# TimerModule.net
KiCad netlist of a schematic drawn in EAGLE
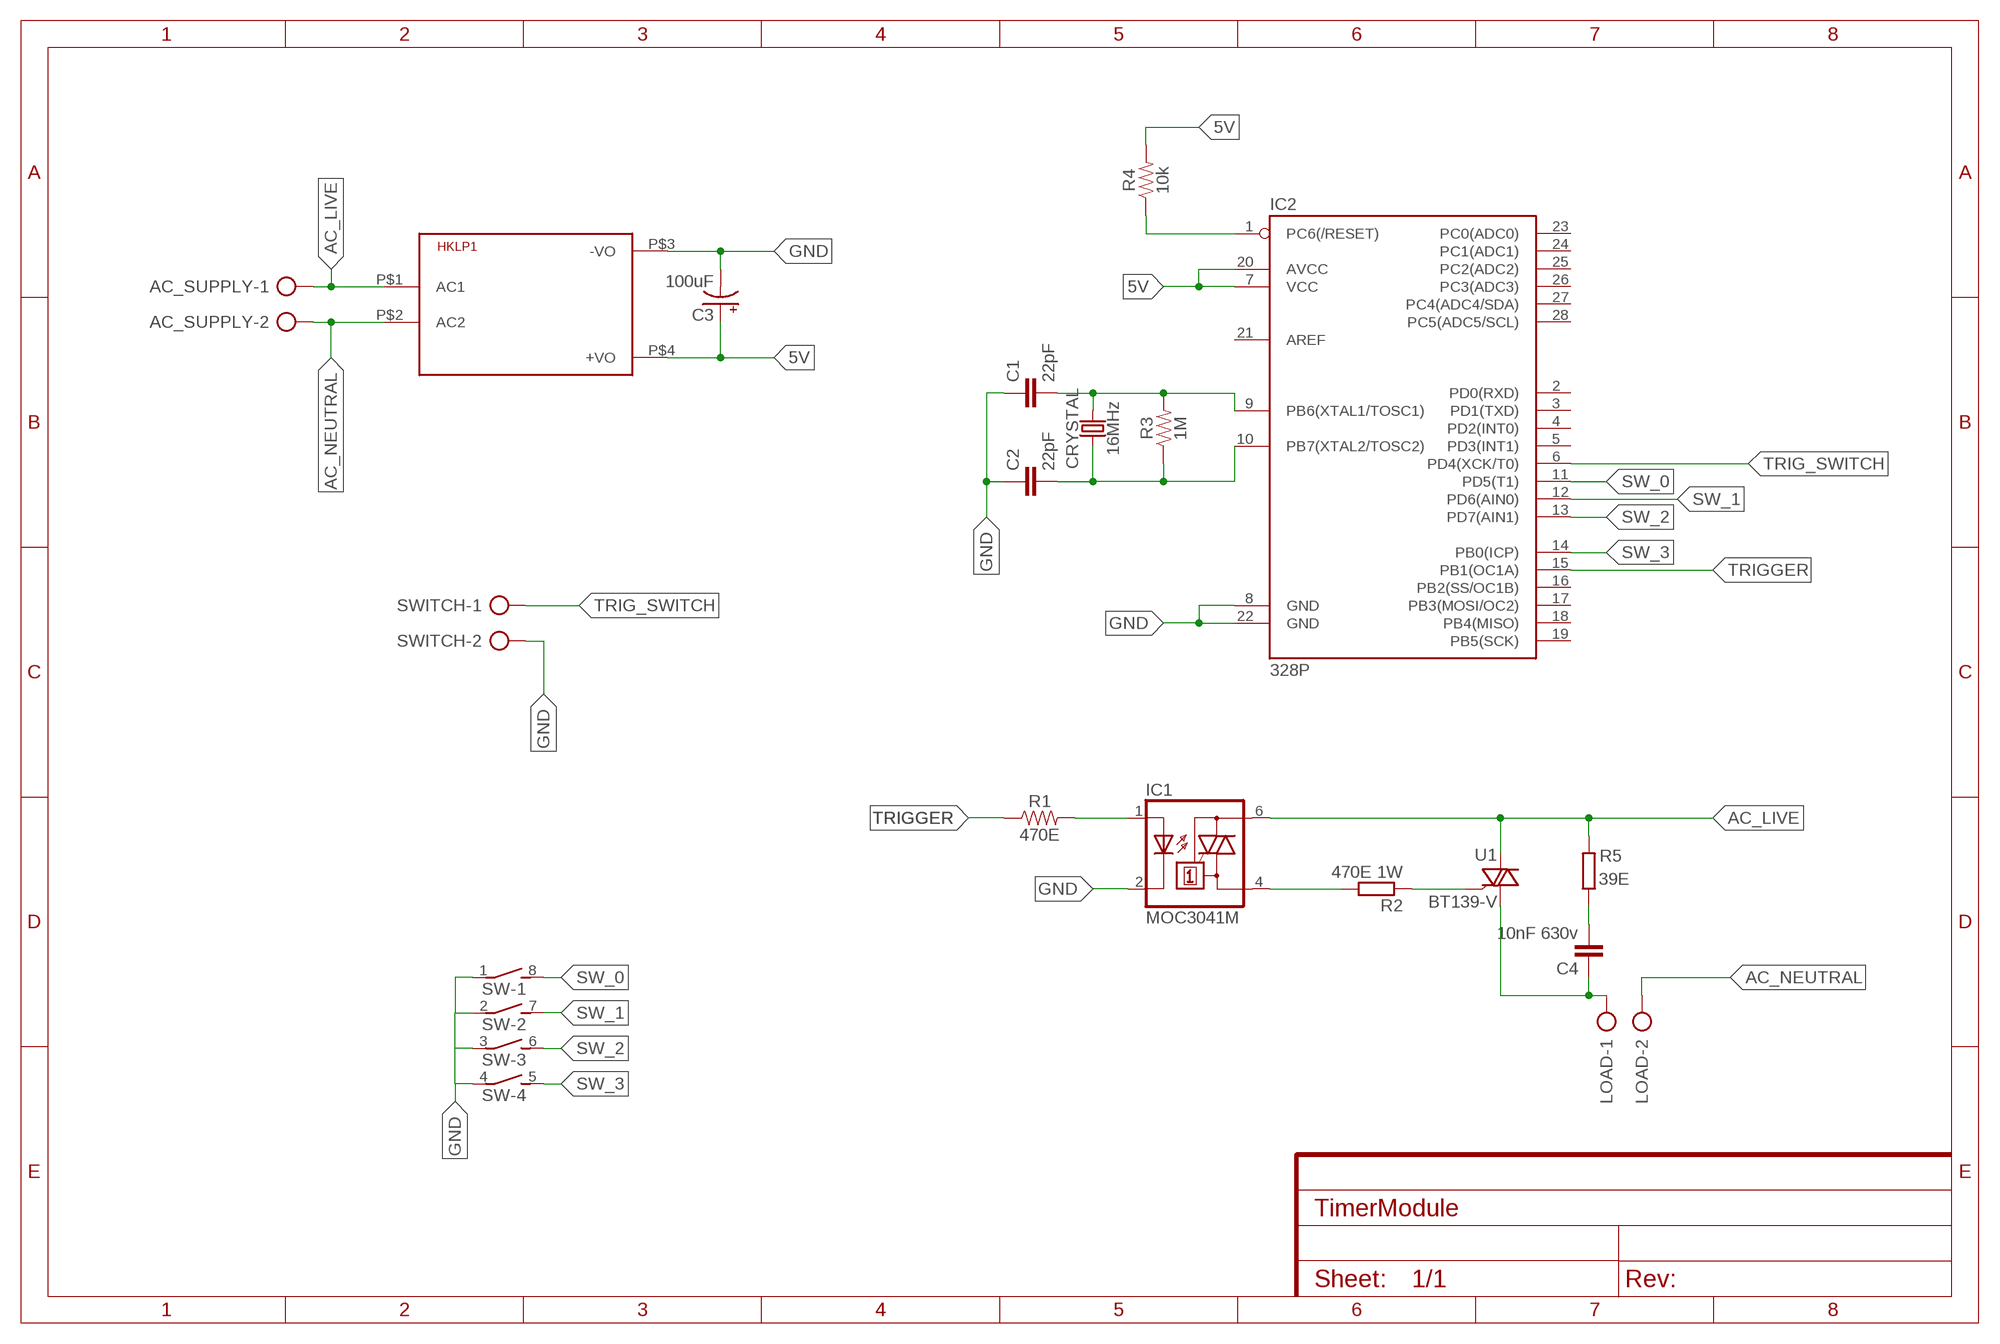
[diagram p0: schematic, sheet 1]

(export (version "E")
  (design (tool "Eeschema 10.0.6"))
  (components
    (comp (ref "AC_SUPPLY")
      (value "AK300/2")
      (footprint "eagle-import:AK300_2")
      (libsource (lib "eagle-import") (part "AK300/2"))
    )
    (comp (ref "C1")
      (value "22pF")
      (footprint "eagle-import:CAP-PTH-2.54")
      (libsource (lib "eagle-import") (part "22PF-PTH-2.54MM-200V-5%"))
    )
    (comp (ref "C2")
      (value "22pF")
      (footprint "eagle-import:CAP-PTH-2.54")
      (libsource (lib "eagle-import") (part "22PF-PTH-2.54MM-200V-5%"))
    )
    (comp (ref "C3")
      (value "100uF")
      (footprint "eagle-import:E2,5-6")
      (libsource (lib "eagle-import") (part "CPOL-USE2.5-6"))
    )
    (comp (ref "C4")
      (value "10nF 630v")
      (footprint "eagle-import:C7.5B3")
      (libsource (lib "eagle-import") (part "C7.5/3"))
    )
    (comp (ref "CRYSTAL")
      (value "16MHz")
      (footprint "eagle-import:HC49US")
      (libsource (lib "eagle-import") (part "CRYSTAL-16MHZPTH-HC49US"))
    )
    (comp (ref "HKLP1")
      (value "HKLPM01")
      (footprint "eagle-import:HKLPM01")
      (libsource (lib "eagle-import") (part "HKLPM01"))
    )
    (comp (ref "IC1")
      (value "MOC3041M")
      (footprint "eagle-import:DIL06")
      (fields (field (name "MF") "FAIRCHILD SEMICONDUCTOR") (field (name "MPN") "MOC3031M"))
      (libsource (lib "eagle-import") (part "MOC3031M"))
    )
    (comp (ref "IC2")
      (value "328P")
      (footprint "eagle-import:DIP28")
      (libsource (lib "eagle-import") (part "ATMEGA328P_PDIP"))
    )
    (comp (ref "LOAD")
      (value "AK300/2")
      (footprint "eagle-import:AK300_2")
      (libsource (lib "eagle-import") (part "AK300/2"))
    )
    (comp (ref "R1")
      (value "470E")
      (footprint "eagle-import:AXIAL-0.3")
      (libsource (lib "eagle-import") (part "1KOHM-HORIZ-1/4W-1%"))
    )
    (comp (ref "R2")
      (value "470E 1W")
      (footprint "eagle-import:0309_10")
      (libsource (lib "eagle-import") (part "R-EU_0309/10"))
    )
    (comp (ref "R3")
      (value "1M")
      (footprint "eagle-import:AXIAL-0.3")
      (libsource (lib "eagle-import") (part "1KOHM-HORIZ-1/4W-1%"))
    )
    (comp (ref "R4")
      (value "10k")
      (footprint "eagle-import:AXIAL-0.3")
      (libsource (lib "eagle-import") (part "1KOHM-HORIZ-1/4W-1%"))
    )
    (comp (ref "R5")
      (value "39E")
      (footprint "eagle-import:0309_10")
      (libsource (lib "eagle-import") (part "R-EU_0309/10"))
    )
    (comp (ref "SW")
      (value "DIP04S")
      (footprint "eagle-import:DIP04S")
      (libsource (lib "eagle-import") (part "DIP04S"))
    )
    (comp (ref "SWITCH")
      (value "AK300/2")
      (footprint "eagle-import:AK300_2")
      (libsource (lib "eagle-import") (part "AK300/2"))
    )
    (comp (ref "U1")
      (value "BT139-V")
      (footprint "eagle-import:TO220BV")
      (libsource (lib "eagle-import") (part "BT138-V"))
    )
  )
  (nets
    (net (code "1") (name "5V") (class "Default")
      (node (ref "C3") (pin "+") (pinfunction "+_+") (pintype "passive"))
      (node (ref "HKLP1") (pin "P$4") (pinfunction "+VO_P$4") (pintype "bidirectional"))
      (node (ref "IC2") (pin "20") (pinfunction "AVCC_20") (pintype "bidirectional"))
      (node (ref "IC2") (pin "7") (pinfunction "VCC_7") (pintype "bidirectional"))
      (node (ref "R4") (pin "P$2") (pinfunction "2_P$2") (pintype "passive"))
    )
    (net (code "2") (name "AC_LIVE") (class "Default")
      (node (ref "AC_SUPPLY") (pin "1") (pinfunction "KL_1") (pintype "passive"))
      (node (ref "HKLP1") (pin "P$1") (pinfunction "AC1_P$1") (pintype "bidirectional"))
      (node (ref "IC1") (pin "6") (pinfunction "A2_6") (pintype "passive"))
      (node (ref "R5") (pin "2") (pinfunction "2_2") (pintype "passive"))
      (node (ref "U1") (pin "T2") (pinfunction "A2_T2") (pintype "passive"))
    )
    (net (code "3") (name "AC_NEUTRAL") (class "Default")
      (node (ref "AC_SUPPLY") (pin "2") (pinfunction "KL_2") (pintype "passive"))
      (node (ref "HKLP1") (pin "P$2") (pinfunction "AC2_P$2") (pintype "bidirectional"))
      (node (ref "LOAD") (pin "2") (pinfunction "KL_2") (pintype "passive"))
    )
    (net (code "4") (name "GND") (class "Default")
      (node (ref "C1") (pin "1") (pinfunction "1_1") (pintype "passive"))
      (node (ref "C2") (pin "1") (pinfunction "1_1") (pintype "passive"))
      (node (ref "C3") (pin "-") (pinfunction "-_-") (pintype "passive"))
      (node (ref "HKLP1") (pin "P$3") (pinfunction "-VO_P$3") (pintype "bidirectional"))
      (node (ref "IC1") (pin "2") (pinfunction "C_2") (pintype "passive"))
      (node (ref "IC2") (pin "22") (pinfunction "GND_22") (pintype "bidirectional"))
      (node (ref "IC2") (pin "8") (pinfunction "GND_8") (pintype "bidirectional"))
      (node (ref "SW") (pin "1") (pinfunction "1_1") (pintype "passive"))
      (node (ref "SW") (pin "2") (pinfunction "1_2") (pintype "passive"))
      (node (ref "SW") (pin "3") (pinfunction "1_3") (pintype "passive"))
      (node (ref "SW") (pin "4") (pinfunction "1_4") (pintype "passive"))
      (node (ref "SWITCH") (pin "2") (pinfunction "KL_2") (pintype "passive"))
    )
    (net (code "5") (name "Net-(C4-Pad2)") (class "Default")
      (node (ref "C4") (pin "2") (pinfunction "2_2") (pintype "passive"))
      (node (ref "R5") (pin "1") (pinfunction "1_1") (pintype "passive"))
    )
    (net (code "6") (name "Net-(IC1-A)") (class "Default")
      (node (ref "IC1") (pin "1") (pinfunction "A_1") (pintype "passive"))
      (node (ref "R1") (pin "P$2") (pinfunction "2_P$2") (pintype "passive"))
    )
    (net (code "7") (name "Net-(IC1-A1)") (class "Default")
      (node (ref "IC1") (pin "4") (pinfunction "A1_4") (pintype "passive"))
      (node (ref "R2") (pin "2") (pinfunction "2_2") (pintype "passive"))
    )
    (net (code "8") (name "Net-(IC2-PB6(XTAL1{slash}TOSC1))") (class "Default")
      (node (ref "C1") (pin "2") (pinfunction "2_2") (pintype "passive"))
      (node (ref "CRYSTAL") (pin "2") (pinfunction "2_2") (pintype "passive"))
      (node (ref "IC2") (pin "9") (pinfunction "PB6(XTAL1/TOSC1)_9") (pintype "bidirectional"))
      (node (ref "R3") (pin "P$2") (pinfunction "2_P$2") (pintype "passive"))
    )
    (net (code "9") (name "Net-(IC2-PB7(XTAL2{slash}TOSC2))") (class "Default")
      (node (ref "C2") (pin "2") (pinfunction "2_2") (pintype "passive"))
      (node (ref "CRYSTAL") (pin "1") (pinfunction "1_1") (pintype "passive"))
      (node (ref "IC2") (pin "10") (pinfunction "PB7(XTAL2/TOSC2)_10") (pintype "bidirectional"))
      (node (ref "R3") (pin "P$1") (pinfunction "1_P$1") (pintype "passive"))
    )
    (net (code "10") (name "Net-(IC2-PC6({slash}RESET))") (class "Default")
      (node (ref "IC2") (pin "1") (pinfunction "PC6(/RESET)_1") (pintype "bidirectional"))
      (node (ref "R4") (pin "P$1") (pinfunction "1_P$1") (pintype "passive"))
    )
    (net (code "11") (name "Net-(LOADA-KL)") (class "Default")
      (node (ref "C4") (pin "1") (pinfunction "1_1") (pintype "passive"))
      (node (ref "LOAD") (pin "1") (pinfunction "KL_1") (pintype "passive"))
      (node (ref "U1") (pin "T1") (pinfunction "A1_T1") (pintype "passive"))
    )
    (net (code "12") (name "Net-(R2-Pad1)") (class "Default")
      (node (ref "R2") (pin "1") (pinfunction "1_1") (pintype "passive"))
      (node (ref "U1") (pin "G") (pinfunction "G_G") (pintype "passive"))
    )
    (net (code "13") (name "SW_0") (class "Default")
      (node (ref "IC2") (pin "11") (pinfunction "PD5(T1)_11") (pintype "bidirectional"))
      (node (ref "SW") (pin "8") (pinfunction "2_8") (pintype "passive"))
    )
    (net (code "14") (name "SW_1") (class "Default")
      (node (ref "IC2") (pin "12") (pinfunction "PD6(AIN0)_12") (pintype "bidirectional"))
      (node (ref "SW") (pin "7") (pinfunction "2_7") (pintype "passive"))
    )
    (net (code "15") (name "SW_2") (class "Default")
      (node (ref "IC2") (pin "13") (pinfunction "PD7(AIN1)_13") (pintype "bidirectional"))
      (node (ref "SW") (pin "6") (pinfunction "2_6") (pintype "passive"))
    )
    (net (code "16") (name "SW_3") (class "Default")
      (node (ref "IC2") (pin "14") (pinfunction "PB0(ICP)_14") (pintype "bidirectional"))
      (node (ref "SW") (pin "5") (pinfunction "2_5") (pintype "passive"))
    )
    (net (code "17") (name "TRIGGER") (class "Default")
      (node (ref "IC2") (pin "15") (pinfunction "PB1(OC1A)_15") (pintype "bidirectional"))
      (node (ref "R1") (pin "P$1") (pinfunction "1_P$1") (pintype "passive"))
    )
    (net (code "18") (name "TRIG_SWITCH") (class "Default")
      (node (ref "IC2") (pin "6") (pinfunction "PD4(XCK/T0)_6") (pintype "bidirectional"))
      (node (ref "SWITCH") (pin "1") (pinfunction "KL_1") (pintype "passive"))
    )
    (net (code "19") (name "unconnected-(IC2-AREF-Pad21)") (class "Default")
      (node (ref "IC2") (pin "21") (pinfunction "AREF_21") (pintype "bidirectional"))
    )
    (net (code "20") (name "unconnected-(IC2-PB2(SS{slash}OC1B)-Pad16)") (class "Default")
      (node (ref "IC2") (pin "16") (pinfunction "PB2(SS/OC1B)_16") (pintype "bidirectional"))
    )
    (net (code "21") (name "unconnected-(IC2-PB3(MOSI{slash}OC2)-Pad17)") (class "Default")
      (node (ref "IC2") (pin "17") (pinfunction "PB3(MOSI/OC2)_17") (pintype "bidirectional"))
    )
    (net (code "22") (name "unconnected-(IC2-PB4(MISO)-Pad18)") (class "Default")
      (node (ref "IC2") (pin "18") (pinfunction "PB4(MISO)_18") (pintype "bidirectional"))
    )
    (net (code "23") (name "unconnected-(IC2-PB5(SCK)-Pad19)") (class "Default")
      (node (ref "IC2") (pin "19") (pinfunction "PB5(SCK)_19") (pintype "bidirectional"))
    )
    (net (code "24") (name "unconnected-(IC2-PC0(ADC0)-Pad23)") (class "Default")
      (node (ref "IC2") (pin "23") (pinfunction "PC0(ADC0)_23") (pintype "bidirectional"))
    )
    (net (code "25") (name "unconnected-(IC2-PC1(ADC1)-Pad24)") (class "Default")
      (node (ref "IC2") (pin "24") (pinfunction "PC1(ADC1)_24") (pintype "bidirectional"))
    )
    (net (code "26") (name "unconnected-(IC2-PC2(ADC2)-Pad25)") (class "Default")
      (node (ref "IC2") (pin "25") (pinfunction "PC2(ADC2)_25") (pintype "bidirectional"))
    )
    (net (code "27") (name "unconnected-(IC2-PC3(ADC3)-Pad26)") (class "Default")
      (node (ref "IC2") (pin "26") (pinfunction "PC3(ADC3)_26") (pintype "bidirectional"))
    )
    (net (code "28") (name "unconnected-(IC2-PC4(ADC4{slash}SDA)-Pad27)") (class "Default")
      (node (ref "IC2") (pin "27") (pinfunction "PC4(ADC4/SDA)_27") (pintype "bidirectional"))
    )
    (net (code "29") (name "unconnected-(IC2-PC5(ADC5{slash}SCL)-Pad28)") (class "Default")
      (node (ref "IC2") (pin "28") (pinfunction "PC5(ADC5/SCL)_28") (pintype "bidirectional"))
    )
    (net (code "30") (name "unconnected-(IC2-PD0(RXD)-Pad2)") (class "Default")
      (node (ref "IC2") (pin "2") (pinfunction "PD0(RXD)_2") (pintype "bidirectional"))
    )
    (net (code "31") (name "unconnected-(IC2-PD1(TXD)-Pad3)") (class "Default")
      (node (ref "IC2") (pin "3") (pinfunction "PD1(TXD)_3") (pintype "bidirectional"))
    )
    (net (code "32") (name "unconnected-(IC2-PD2(INT0)-Pad4)") (class "Default")
      (node (ref "IC2") (pin "4") (pinfunction "PD2(INT0)_4") (pintype "bidirectional"))
    )
    (net (code "33") (name "unconnected-(IC2-PD3(INT1)-Pad5)") (class "Default")
      (node (ref "IC2") (pin "5") (pinfunction "PD3(INT1)_5") (pintype "bidirectional"))
    )
  )
)
